# electrode_module3_3.net
KiCad netlist of a schematic drawn in Altium Designer
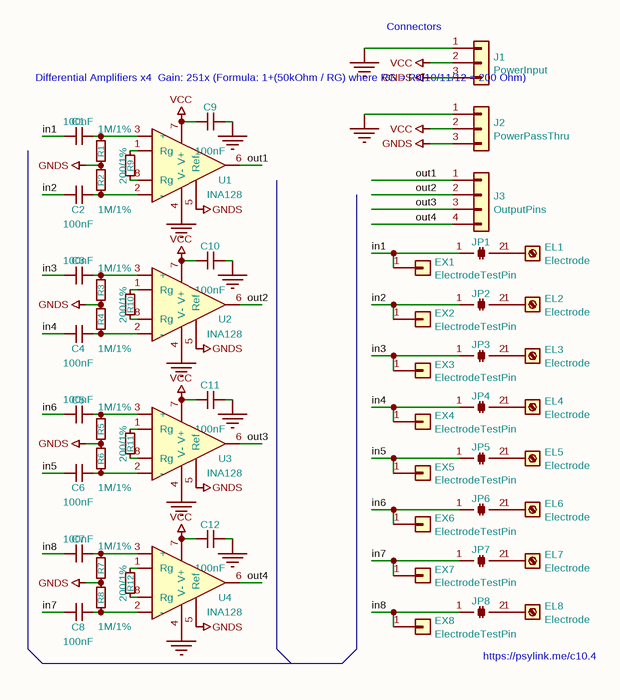
[diagram p0: electrode_module3.3.SchDoc]

(export (version "E")
  (design (tool "Eeschema 10.0.6"))
  (components
    (comp (ref "C1") (value "100nF") (libsource (lib "Device") (part "C_Small")))
    (comp (ref "C2") (value "100nF") (libsource (lib "Device") (part "C_Small")))
    (comp (ref "C3") (value "100nF") (libsource (lib "Device") (part "C_Small")))
    (comp (ref "C4") (value "100nF") (libsource (lib "Device") (part "C_Small")))
    (comp (ref "C5") (value "100nF") (libsource (lib "Device") (part "C_Small")))
    (comp (ref "C6") (value "100nF") (libsource (lib "Device") (part "C_Small")))
    (comp (ref "C7") (value "100nF") (libsource (lib "Device") (part "C_Small")))
    (comp (ref "C8") (value "100nF") (libsource (lib "Device") (part "C_Small")))
    (comp (ref "C9") (value "100nF") (libsource (lib "Device") (part "C_Small")))
    (comp (ref "C10") (value "100nF") (libsource (lib "Device") (part "C_Small")))
    (comp (ref "C11") (value "100nF") (libsource (lib "Device") (part "C_Small")))
    (comp (ref "C12") (value "100nF") (libsource (lib "Device") (part "C_Small")))
    (comp (ref "EL1") (value "Electrode") (libsource (lib "Connector") (part "Screw_Terminal_01x01")))
    (comp (ref "EL2") (value "Electrode") (libsource (lib "Connector") (part "Screw_Terminal_01x01")))
    (comp (ref "EL3") (value "Electrode") (libsource (lib "Connector") (part "Screw_Terminal_01x01")))
    (comp (ref "EL4") (value "Electrode") (libsource (lib "Connector") (part "Screw_Terminal_01x01")))
    (comp (ref "EL5") (value "Electrode") (libsource (lib "Connector") (part "Screw_Terminal_01x01")))
    (comp (ref "EL6") (value "Electrode") (libsource (lib "Connector") (part "Screw_Terminal_01x01")))
    (comp (ref "EL7") (value "Electrode") (libsource (lib "Connector") (part "Screw_Terminal_01x01")))
    (comp (ref "EL8") (value "Electrode") (libsource (lib "Connector") (part "Screw_Terminal_01x01")))
    (comp (ref "EX1") (value "ElectrodeTestPin") (libsource (lib "Connector_Generic") (part "Conn_01x01")))
    (comp (ref "EX2") (value "ElectrodeTestPin") (libsource (lib "Connector_Generic") (part "Conn_01x01")))
    (comp (ref "EX3") (value "ElectrodeTestPin") (libsource (lib "Connector_Generic") (part "Conn_01x01")))
    (comp (ref "EX4") (value "ElectrodeTestPin") (libsource (lib "Connector_Generic") (part "Conn_01x01")))
    (comp (ref "EX5") (value "ElectrodeTestPin") (libsource (lib "Connector_Generic") (part "Conn_01x01")))
    (comp (ref "EX6") (value "ElectrodeTestPin") (libsource (lib "Connector_Generic") (part "Conn_01x01")))
    (comp (ref "EX7") (value "ElectrodeTestPin") (libsource (lib "Connector_Generic") (part "Conn_01x01")))
    (comp (ref "EX8") (value "ElectrodeTestPin") (libsource (lib "Connector_Generic") (part "Conn_01x01")))
    (comp (ref "J1") (value "PowerInput") (libsource (lib "Connector_Generic") (part "Conn_01x03")))
    (comp (ref "J2") (value "PowerPassThru") (libsource (lib "Connector_Generic") (part "Conn_01x03")))
    (comp (ref "J3") (value "OutputPins") (libsource (lib "Connector_Generic") (part "Conn_01x04")))
    (comp (ref "JP1")
      (value "SolderJumper_2_Bridged")
      (libsource (lib "Jumper") (part "SolderJumper_2_Bridged"))
    )
    (comp (ref "JP2")
      (value "SolderJumper_2_Bridged")
      (libsource (lib "Jumper") (part "SolderJumper_2_Bridged"))
    )
    (comp (ref "JP3")
      (value "SolderJumper_2_Bridged")
      (libsource (lib "Jumper") (part "SolderJumper_2_Bridged"))
    )
    (comp (ref "JP4")
      (value "SolderJumper_2_Bridged")
      (libsource (lib "Jumper") (part "SolderJumper_2_Bridged"))
    )
    (comp (ref "JP5")
      (value "SolderJumper_2_Bridged")
      (libsource (lib "Jumper") (part "SolderJumper_2_Bridged"))
    )
    (comp (ref "JP6")
      (value "SolderJumper_2_Bridged")
      (libsource (lib "Jumper") (part "SolderJumper_2_Bridged"))
    )
    (comp (ref "JP7")
      (value "SolderJumper_2_Bridged")
      (libsource (lib "Jumper") (part "SolderJumper_2_Bridged"))
    )
    (comp (ref "JP8")
      (value "SolderJumper_2_Bridged")
      (libsource (lib "Jumper") (part "SolderJumper_2_Bridged"))
    )
    (comp (ref "R1") (value "1M/1%") (libsource (lib "Device") (part "R_Small")))
    (comp (ref "R2") (value "1M/1%") (libsource (lib "Device") (part "R_Small")))
    (comp (ref "R3") (value "1M/1%") (libsource (lib "Device") (part "R_Small")))
    (comp (ref "R4") (value "1M/1%") (libsource (lib "Device") (part "R_Small")))
    (comp (ref "R5") (value "1M/1%") (libsource (lib "Device") (part "R_Small")))
    (comp (ref "R6") (value "1M/1%") (libsource (lib "Device") (part "R_Small")))
    (comp (ref "R7") (value "1M/1%") (libsource (lib "Device") (part "R_Small")))
    (comp (ref "R8") (value "1M/1%") (libsource (lib "Device") (part "R_Small")))
    (comp (ref "R9") (value "200/1%") (libsource (lib "Device") (part "R_Small")))
    (comp (ref "R10") (value "200/1%") (libsource (lib "Device") (part "R_Small")))
    (comp (ref "R11") (value "200/1%") (libsource (lib "Device") (part "R_Small")))
    (comp (ref "R12") (value "200/1%") (libsource (lib "Device") (part "R_Small")))
    (comp (ref "U1") (value "INA128") (libsource (lib "Amplifier_Instrumentation") (part "INA128")))
    (comp (ref "U2") (value "INA128") (libsource (lib "Amplifier_Instrumentation") (part "INA128")))
    (comp (ref "U3") (value "INA128") (libsource (lib "Amplifier_Instrumentation") (part "INA128")))
    (comp (ref "U4") (value "INA128") (libsource (lib "Amplifier_Instrumentation") (part "INA128")))
  )
  (nets
    (net (code "1") (name "/in1") (class "Default")
      (node (ref "C1") (pin "1") (pinfunction "1_1") (pintype "passive"))
      (node (ref "EX1") (pin "1") (pinfunction "Pin_1_1") (pintype "passive"))
      (node (ref "JP1") (pin "1") (pinfunction "A_1") (pintype "passive"))
    )
    (net (code "2") (name "/in2") (class "Default")
      (node (ref "C2") (pin "2") (pinfunction "2_2") (pintype "passive"))
      (node (ref "EX2") (pin "1") (pinfunction "Pin_1_1") (pintype "passive"))
      (node (ref "JP2") (pin "1") (pinfunction "A_1") (pintype "passive"))
    )
    (net (code "3") (name "/in3") (class "Default")
      (node (ref "C3") (pin "1") (pinfunction "1_1") (pintype "passive"))
      (node (ref "EX3") (pin "1") (pinfunction "Pin_1_1") (pintype "passive"))
      (node (ref "JP3") (pin "1") (pinfunction "A_1") (pintype "passive"))
    )
    (net (code "4") (name "/in4") (class "Default")
      (node (ref "C4") (pin "2") (pinfunction "2_2") (pintype "passive"))
      (node (ref "EX4") (pin "1") (pinfunction "Pin_1_1") (pintype "passive"))
      (node (ref "JP4") (pin "1") (pinfunction "A_1") (pintype "passive"))
    )
    (net (code "5") (name "/in5") (class "Default")
      (node (ref "C6") (pin "2") (pinfunction "2_2") (pintype "passive"))
      (node (ref "EX5") (pin "1") (pinfunction "Pin_1_1") (pintype "passive"))
      (node (ref "JP5") (pin "1") (pinfunction "A_1") (pintype "passive"))
    )
    (net (code "6") (name "/in6") (class "Default")
      (node (ref "C5") (pin "1") (pinfunction "1_1") (pintype "passive"))
      (node (ref "EX6") (pin "1") (pinfunction "Pin_1_1") (pintype "passive"))
      (node (ref "JP6") (pin "1") (pinfunction "A_1") (pintype "passive"))
    )
    (net (code "7") (name "/in7") (class "Default")
      (node (ref "C8") (pin "2") (pinfunction "2_2") (pintype "passive"))
      (node (ref "EX7") (pin "1") (pinfunction "Pin_1_1") (pintype "passive"))
      (node (ref "JP7") (pin "1") (pinfunction "A_1") (pintype "passive"))
    )
    (net (code "8") (name "/in8") (class "Default")
      (node (ref "C7") (pin "1") (pinfunction "1_1") (pintype "passive"))
      (node (ref "EX8") (pin "1") (pinfunction "Pin_1_1") (pintype "passive"))
      (node (ref "JP8") (pin "1") (pinfunction "A_1") (pintype "passive"))
    )
    (net (code "9") (name "/out1") (class "Default")
      (node (ref "J3") (pin "1") (pinfunction "Pin_1_1") (pintype "passive"))
      (node (ref "U1") (pin "6") (pinfunction "6_6") (pintype "passive"))
    )
    (net (code "10") (name "/out2") (class "Default")
      (node (ref "J3") (pin "2") (pinfunction "Pin_2_2") (pintype "passive"))
      (node (ref "U2") (pin "6") (pinfunction "6_6") (pintype "passive"))
    )
    (net (code "11") (name "/out3") (class "Default")
      (node (ref "J3") (pin "3") (pinfunction "Pin_3_3") (pintype "passive"))
      (node (ref "U3") (pin "6") (pinfunction "6_6") (pintype "passive"))
    )
    (net (code "12") (name "/out4") (class "Default")
      (node (ref "J3") (pin "4") (pinfunction "Pin_4_4") (pintype "passive"))
      (node (ref "U4") (pin "6") (pinfunction "6_6") (pintype "passive"))
    )
    (net (code "13") (name "Earth") (class "Default")
      (node (ref "C10") (pin "2") (pinfunction "2_2") (pintype "passive"))
      (node (ref "C11") (pin "2") (pinfunction "2_2") (pintype "passive"))
      (node (ref "C12") (pin "2") (pinfunction "2_2") (pintype "passive"))
      (node (ref "C9") (pin "2") (pinfunction "2_2") (pintype "passive"))
      (node (ref "J1") (pin "1") (pinfunction "Pin_1_1") (pintype "passive"))
      (node (ref "J2") (pin "1") (pinfunction "Pin_1_1") (pintype "passive"))
      (node (ref "U1") (pin "4") (pinfunction "V-_4") (pintype "passive"))
      (node (ref "U2") (pin "4") (pinfunction "V-_4") (pintype "passive"))
      (node (ref "U3") (pin "4") (pinfunction "V-_4") (pintype "passive"))
      (node (ref "U4") (pin "4") (pinfunction "V-_4") (pintype "passive"))
    )
    (net (code "14") (name "GNDS") (class "Default")
      (node (ref "J1") (pin "3") (pinfunction "Pin_3_3") (pintype "passive"))
      (node (ref "J2") (pin "3") (pinfunction "Pin_3_3") (pintype "passive"))
      (node (ref "R1") (pin "2") (pinfunction "2_2") (pintype "passive"))
      (node (ref "R2") (pin "1") (pinfunction "1_1") (pintype "passive"))
      (node (ref "R3") (pin "2") (pinfunction "2_2") (pintype "passive"))
      (node (ref "R4") (pin "1") (pinfunction "1_1") (pintype "passive"))
      (node (ref "R5") (pin "2") (pinfunction "2_2") (pintype "passive"))
      (node (ref "R6") (pin "1") (pinfunction "1_1") (pintype "passive"))
      (node (ref "R7") (pin "2") (pinfunction "2_2") (pintype "passive"))
      (node (ref "R8") (pin "1") (pinfunction "1_1") (pintype "passive"))
      (node (ref "U1") (pin "5") (pinfunction "Ref_5") (pintype "passive"))
      (node (ref "U2") (pin "5") (pinfunction "Ref_5") (pintype "passive"))
      (node (ref "U3") (pin "5") (pinfunction "Ref_5") (pintype "passive"))
      (node (ref "U4") (pin "5") (pinfunction "Ref_5") (pintype "passive"))
    )
    (net (code "15") (name "Net-(EL1-Pin_1)") (class "Default")
      (node (ref "EL1") (pin "1") (pinfunction "Pin_1_1") (pintype "passive"))
      (node (ref "JP1") (pin "2") (pinfunction "B_2") (pintype "passive"))
    )
    (net (code "16") (name "Net-(EL2-Pin_1)") (class "Default")
      (node (ref "EL2") (pin "1") (pinfunction "Pin_1_1") (pintype "passive"))
      (node (ref "JP2") (pin "2") (pinfunction "B_2") (pintype "passive"))
    )
    (net (code "17") (name "Net-(EL3-Pin_1)") (class "Default")
      (node (ref "EL3") (pin "1") (pinfunction "Pin_1_1") (pintype "passive"))
      (node (ref "JP3") (pin "2") (pinfunction "B_2") (pintype "passive"))
    )
    (net (code "18") (name "Net-(EL4-Pin_1)") (class "Default")
      (node (ref "EL4") (pin "1") (pinfunction "Pin_1_1") (pintype "passive"))
      (node (ref "JP4") (pin "2") (pinfunction "B_2") (pintype "passive"))
    )
    (net (code "19") (name "Net-(EL5-Pin_1)") (class "Default")
      (node (ref "EL5") (pin "1") (pinfunction "Pin_1_1") (pintype "passive"))
      (node (ref "JP5") (pin "2") (pinfunction "B_2") (pintype "passive"))
    )
    (net (code "20") (name "Net-(EL6-Pin_1)") (class "Default")
      (node (ref "EL6") (pin "1") (pinfunction "Pin_1_1") (pintype "passive"))
      (node (ref "JP6") (pin "2") (pinfunction "B_2") (pintype "passive"))
    )
    (net (code "21") (name "Net-(EL7-Pin_1)") (class "Default")
      (node (ref "EL7") (pin "1") (pinfunction "Pin_1_1") (pintype "passive"))
      (node (ref "JP7") (pin "2") (pinfunction "B_2") (pintype "passive"))
    )
    (net (code "22") (name "Net-(EL8-Pin_1)") (class "Default")
      (node (ref "EL8") (pin "1") (pinfunction "Pin_1_1") (pintype "passive"))
      (node (ref "JP8") (pin "2") (pinfunction "B_2") (pintype "passive"))
    )
    (net (code "23") (name "Net-(R9-Pad1)") (class "Default")
      (node (ref "R9") (pin "1") (pinfunction "1_1") (pintype "passive"))
      (node (ref "U1") (pin "1") (pinfunction "Rg_1") (pintype "passive"))
    )
    (net (code "24") (name "Net-(R9-Pad2)") (class "Default")
      (node (ref "R9") (pin "2") (pinfunction "2_2") (pintype "passive"))
      (node (ref "U1") (pin "8") (pinfunction "Rg_8") (pintype "passive"))
    )
    (net (code "25") (name "Net-(R10-Pad1)") (class "Default")
      (node (ref "R10") (pin "1") (pinfunction "1_1") (pintype "passive"))
      (node (ref "U2") (pin "1") (pinfunction "Rg_1") (pintype "passive"))
    )
    (net (code "26") (name "Net-(R10-Pad2)") (class "Default")
      (node (ref "R10") (pin "2") (pinfunction "2_2") (pintype "passive"))
      (node (ref "U2") (pin "8") (pinfunction "Rg_8") (pintype "passive"))
    )
    (net (code "27") (name "Net-(R11-Pad1)") (class "Default")
      (node (ref "R11") (pin "1") (pinfunction "1_1") (pintype "passive"))
      (node (ref "U3") (pin "1") (pinfunction "Rg_1") (pintype "passive"))
    )
    (net (code "28") (name "Net-(R11-Pad2)") (class "Default")
      (node (ref "R11") (pin "2") (pinfunction "2_2") (pintype "passive"))
      (node (ref "U3") (pin "8") (pinfunction "Rg_8") (pintype "passive"))
    )
    (net (code "29") (name "Net-(R12-Pad1)") (class "Default")
      (node (ref "R12") (pin "1") (pinfunction "1_1") (pintype "passive"))
      (node (ref "U4") (pin "1") (pinfunction "Rg_1") (pintype "passive"))
    )
    (net (code "30") (name "Net-(R12-Pad2)") (class "Default")
      (node (ref "R12") (pin "2") (pinfunction "2_2") (pintype "passive"))
      (node (ref "U4") (pin "8") (pinfunction "Rg_8") (pintype "passive"))
    )
    (net (code "31") (name "Net-(U1-+)") (class "Default")
      (node (ref "C1") (pin "2") (pinfunction "2_2") (pintype "passive"))
      (node (ref "R1") (pin "1") (pinfunction "1_1") (pintype "passive"))
      (node (ref "U1") (pin "3") (pinfunction "+_3") (pintype "passive"))
    )
    (net (code "32") (name "Net-(U1--)") (class "Default")
      (node (ref "C2") (pin "1") (pinfunction "1_1") (pintype "passive"))
      (node (ref "R2") (pin "2") (pinfunction "2_2") (pintype "passive"))
      (node (ref "U1") (pin "2") (pinfunction "-_2") (pintype "passive"))
    )
    (net (code "33") (name "Net-(U2-+)") (class "Default")
      (node (ref "C3") (pin "2") (pinfunction "2_2") (pintype "passive"))
      (node (ref "R3") (pin "1") (pinfunction "1_1") (pintype "passive"))
      (node (ref "U2") (pin "3") (pinfunction "+_3") (pintype "passive"))
    )
    (net (code "34") (name "Net-(U2--)") (class "Default")
      (node (ref "C4") (pin "1") (pinfunction "1_1") (pintype "passive"))
      (node (ref "R4") (pin "2") (pinfunction "2_2") (pintype "passive"))
      (node (ref "U2") (pin "2") (pinfunction "-_2") (pintype "passive"))
    )
    (net (code "35") (name "Net-(U3-+)") (class "Default")
      (node (ref "C5") (pin "2") (pinfunction "2_2") (pintype "passive"))
      (node (ref "R5") (pin "1") (pinfunction "1_1") (pintype "passive"))
      (node (ref "U3") (pin "3") (pinfunction "+_3") (pintype "passive"))
    )
    (net (code "36") (name "Net-(U3--)") (class "Default")
      (node (ref "C6") (pin "1") (pinfunction "1_1") (pintype "passive"))
      (node (ref "R6") (pin "2") (pinfunction "2_2") (pintype "passive"))
      (node (ref "U3") (pin "2") (pinfunction "-_2") (pintype "passive"))
    )
    (net (code "37") (name "Net-(U4-+)") (class "Default")
      (node (ref "C7") (pin "2") (pinfunction "2_2") (pintype "passive"))
      (node (ref "R7") (pin "1") (pinfunction "1_1") (pintype "passive"))
      (node (ref "U4") (pin "3") (pinfunction "+_3") (pintype "passive"))
    )
    (net (code "38") (name "Net-(U4--)") (class "Default")
      (node (ref "C8") (pin "1") (pinfunction "1_1") (pintype "passive"))
      (node (ref "R8") (pin "2") (pinfunction "2_2") (pintype "passive"))
      (node (ref "U4") (pin "2") (pinfunction "-_2") (pintype "passive"))
    )
    (net (code "39") (name "VCC") (class "Default")
      (node (ref "C10") (pin "1") (pinfunction "1_1") (pintype "passive"))
      (node (ref "C11") (pin "1") (pinfunction "1_1") (pintype "passive"))
      (node (ref "C12") (pin "1") (pinfunction "1_1") (pintype "passive"))
      (node (ref "C9") (pin "1") (pinfunction "1_1") (pintype "passive"))
      (node (ref "J1") (pin "2") (pinfunction "Pin_2_2") (pintype "passive"))
      (node (ref "J2") (pin "2") (pinfunction "Pin_2_2") (pintype "passive"))
      (node (ref "U1") (pin "7") (pinfunction "V+_7") (pintype "passive"))
      (node (ref "U2") (pin "7") (pinfunction "V+_7") (pintype "passive"))
      (node (ref "U3") (pin "7") (pinfunction "V+_7") (pintype "passive"))
      (node (ref "U4") (pin "7") (pinfunction "V+_7") (pintype "passive"))
    )
  )
)
